# PicoBoard.net
KiCad netlist of a schematic drawn in EAGLE
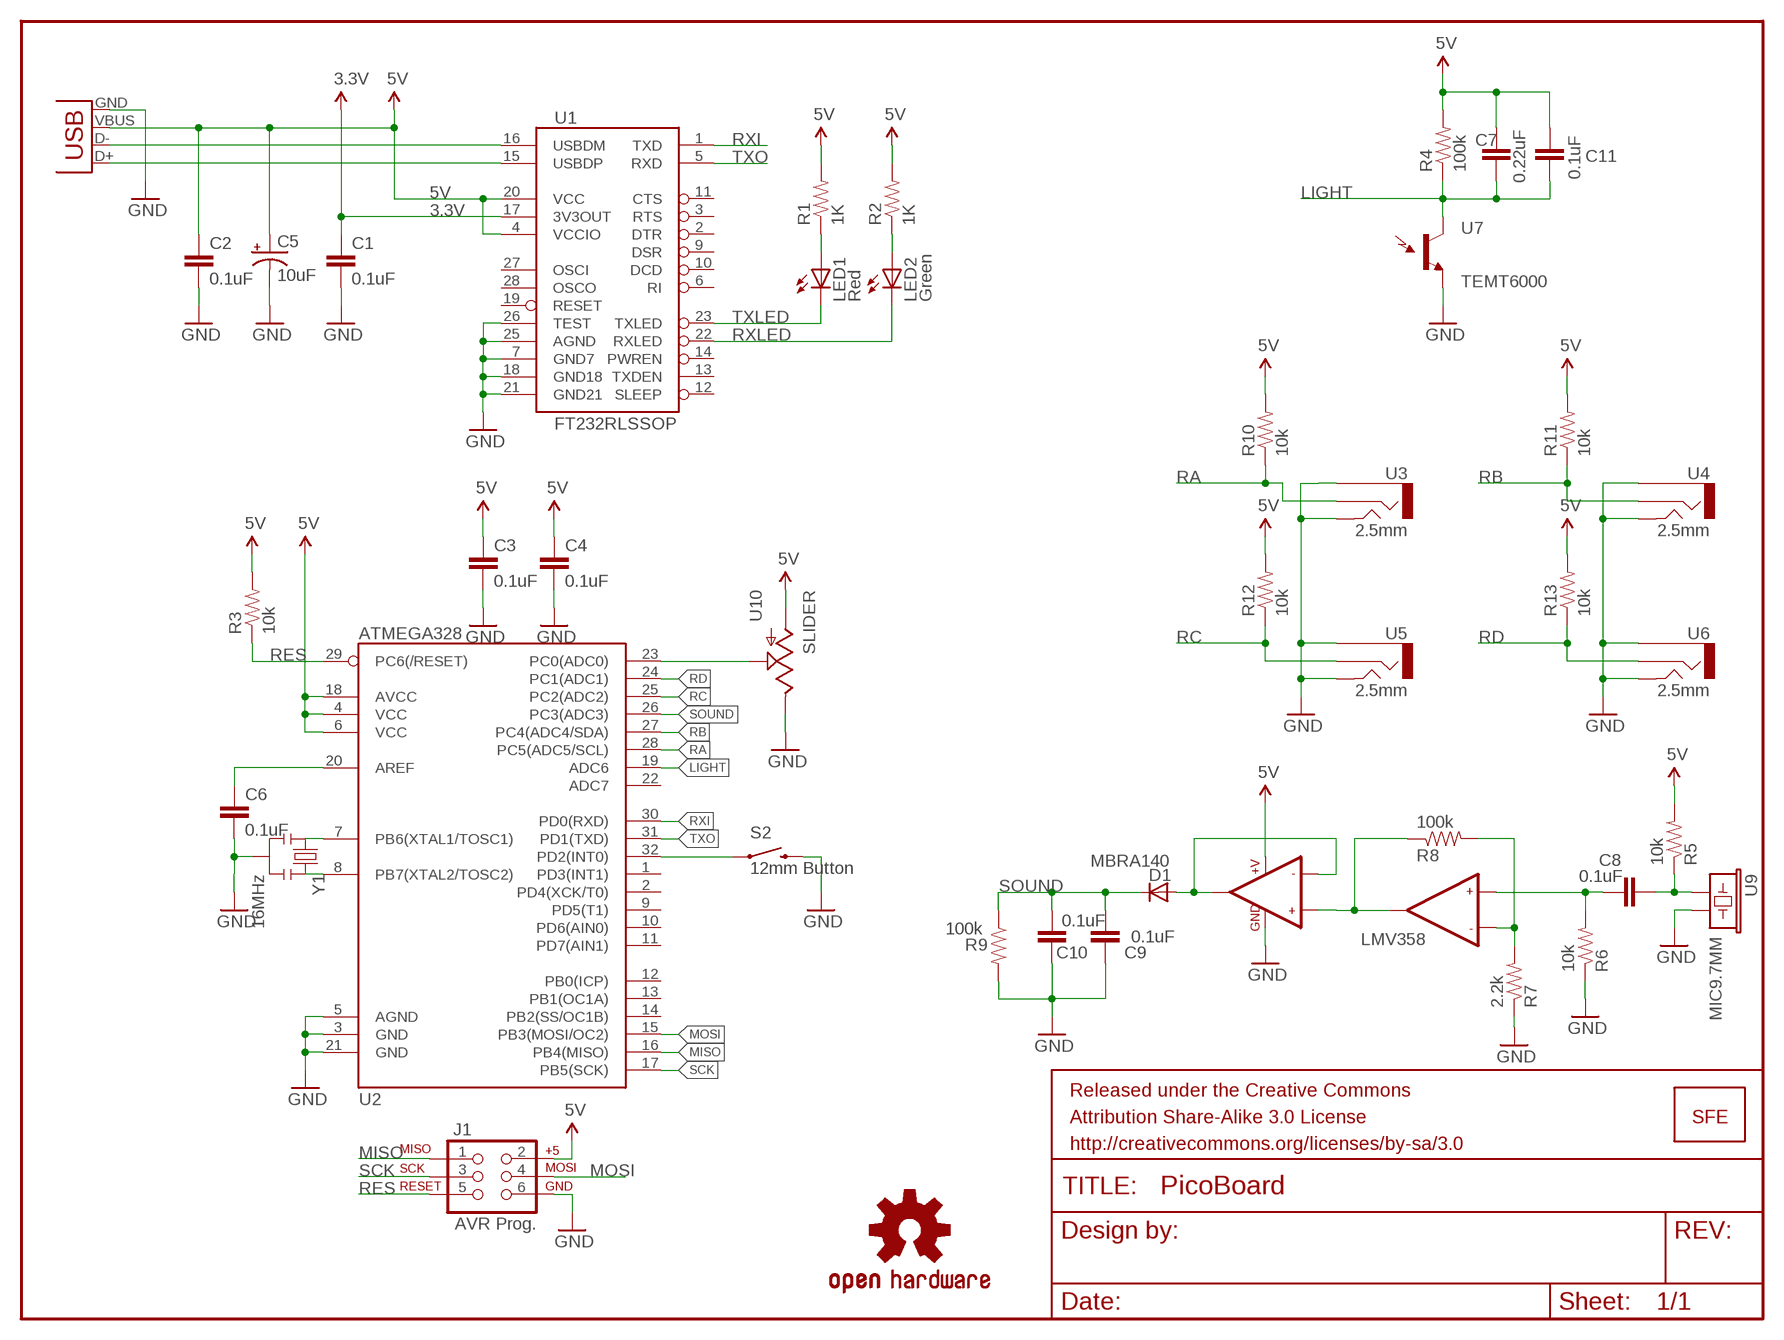
[diagram p0: schematic, sheet 1]

(export (version "E")
  (design (tool "Eeschema 10.0.6"))
  (components
    (comp (ref "C1")
      (value "0.1uF")
      (footprint "eagle-import:0603-CAP")
      (libsource (lib "eagle-import") (part "CAP0603-CAP"))
    )
    (comp (ref "C2")
      (value "0.1uF")
      (footprint "eagle-import:0603-CAP")
      (libsource (lib "eagle-import") (part "CAP0603-CAP"))
    )
    (comp (ref "C3")
      (value "0.1uF")
      (footprint "eagle-import:0603-CAP")
      (libsource (lib "eagle-import") (part "CAP0603-CAP"))
    )
    (comp (ref "C4")
      (value "0.1uF")
      (footprint "eagle-import:0603-CAP")
      (libsource (lib "eagle-import") (part "CAP0603-CAP"))
    )
    (comp (ref "C5")
      (value "10uF")
      (footprint "eagle-import:EIA3216")
      (libsource (lib "eagle-import") (part "CAP_POL1206"))
    )
    (comp (ref "C6")
      (value "0.1uF")
      (footprint "eagle-import:0603-CAP")
      (libsource (lib "eagle-import") (part "CAP0603-CAP"))
    )
    (comp (ref "C7")
      (value "0.22uF")
      (footprint "eagle-import:0603-CAP")
      (libsource (lib "eagle-import") (part "CAP0603-CAP"))
    )
    (comp (ref "C8")
      (value "0.1uF")
      (footprint "eagle-import:0603-CAP")
      (libsource (lib "eagle-import") (part "CAP0603-CAP"))
    )
    (comp (ref "C9")
      (value "0.1uF")
      (footprint "eagle-import:0603-CAP")
      (libsource (lib "eagle-import") (part "CAP0603-CAP"))
    )
    (comp (ref "C10")
      (value "0.1uF")
      (footprint "eagle-import:0603-CAP")
      (libsource (lib "eagle-import") (part "CAP0603-CAP"))
    )
    (comp (ref "C11")
      (value "0.1uF")
      (footprint "eagle-import:0603-CAP")
      (libsource (lib "eagle-import") (part "CAP0603-CAP"))
    )
    (comp (ref "D1")
      (value "MBRA140")
      (footprint "eagle-import:SMA-DIODE")
      (libsource (lib "eagle-import") (part "DIODESMA"))
    )
    (comp (ref "FRAME1")
      (value "FRAME-LETTER")
      (footprint "eagle-import:CREATIVE_COMMONS")
      (libsource (lib "eagle-import") (part "FRAME-LETTER"))
    )
    (comp (ref "J1")
      (value "AVR Prog.")
      (footprint "eagle-import:2X3")
      (libsource (lib "eagle-import") (part "AVR_SPI_PRG_6PTH"))
    )
    (comp (ref "JP1")
      (value "LOGO-SFENEW")
      (footprint "eagle-import:SFE-NEW-WEBLOGO")
      (libsource (lib "eagle-import") (part "LOGO-SFENEW"))
    )
    (comp (ref "LED1")
      (value "Red")
      (footprint "eagle-import:LED-0603")
      (libsource (lib "eagle-import") (part "LED0603"))
    )
    (comp (ref "LED2")
      (value "Green")
      (footprint "eagle-import:LED-0603")
      (libsource (lib "eagle-import") (part "LED0603"))
    )
    (comp (ref "LOGO1")
      (value "OSHW-LOGOL")
      (footprint "eagle-import:OSHW-LOGO-L")
      (libsource (lib "eagle-import") (part "OSHW-LOGOL"))
    )
    (comp (ref "R1")
      (value "1K")
      (footprint "eagle-import:0603-RES")
      (libsource (lib "eagle-import") (part "RESISTOR0603-RES"))
    )
    (comp (ref "R2")
      (value "1K")
      (footprint "eagle-import:0603-RES")
      (libsource (lib "eagle-import") (part "RESISTOR0603-RES"))
    )
    (comp (ref "R3")
      (value "10k")
      (footprint "eagle-import:0603-RES")
      (libsource (lib "eagle-import") (part "RESISTOR0603-RES"))
    )
    (comp (ref "R4")
      (value "100k")
      (footprint "eagle-import:0603-RES")
      (libsource (lib "eagle-import") (part "RESISTOR0603-RES"))
    )
    (comp (ref "R5")
      (value "10k")
      (footprint "eagle-import:0603-RES")
      (libsource (lib "eagle-import") (part "RESISTOR0603-RES"))
    )
    (comp (ref "R6")
      (value "10k")
      (footprint "eagle-import:0603-RES")
      (libsource (lib "eagle-import") (part "RESISTOR0603-RES"))
    )
    (comp (ref "R7")
      (value "2.2k")
      (footprint "eagle-import:0603-RES")
      (libsource (lib "eagle-import") (part "RESISTOR0603-RES"))
    )
    (comp (ref "R8")
      (value "100k")
      (footprint "eagle-import:0603-RES")
      (libsource (lib "eagle-import") (part "RESISTOR0603-RES"))
    )
    (comp (ref "R9")
      (value "100k")
      (footprint "eagle-import:0603-RES")
      (libsource (lib "eagle-import") (part "RESISTOR0603-RES"))
    )
    (comp (ref "R10")
      (value "10k")
      (footprint "eagle-import:0603-RES")
      (libsource (lib "eagle-import") (part "RESISTOR0603-RES"))
    )
    (comp (ref "R11")
      (value "10k")
      (footprint "eagle-import:0603-RES")
      (libsource (lib "eagle-import") (part "RESISTOR0603-RES"))
    )
    (comp (ref "R12")
      (value "10k")
      (footprint "eagle-import:0603-RES")
      (libsource (lib "eagle-import") (part "RESISTOR0603-RES"))
    )
    (comp (ref "R13")
      (value "10k")
      (footprint "eagle-import:0603-RES")
      (libsource (lib "eagle-import") (part "RESISTOR0603-RES"))
    )
    (comp (ref "S2")
      (value "12mm Button")
      (footprint "eagle-import:TACTILE-PTH-12MM")
      (libsource (lib "eagle-import") (part "SWITCH-MOMENTARY-212MM"))
    )
    (comp (ref "U1")
      (value "FT232RLSSOP")
      (footprint "eagle-import:SSOP28DB")
      (libsource (lib "eagle-import") (part "FT232RLSSOP"))
    )
    (comp (ref "U2")
      (value "ATMEGA328")
      (footprint "eagle-import:TQFP32-08")
      (libsource (lib "eagle-import") (part "ATMEGA168"))
    )
    (comp (ref "U3")
      (value "2.5mm")
      (footprint "eagle-import:STEREOJACK2.5MM_SMD")
      (libsource (lib "eagle-import") (part "AUDIO-JACKSMD"))
    )
    (comp (ref "U4")
      (value "2.5mm")
      (footprint "eagle-import:STEREOJACK2.5MM_SMD")
      (libsource (lib "eagle-import") (part "AUDIO-JACKSMD"))
    )
    (comp (ref "U5")
      (value "2.5mm")
      (footprint "eagle-import:STEREOJACK2.5MM_SMD")
      (libsource (lib "eagle-import") (part "AUDIO-JACKSMD"))
    )
    (comp (ref "U6")
      (value "2.5mm")
      (footprint "eagle-import:STEREOJACK2.5MM_SMD")
      (libsource (lib "eagle-import") (part "AUDIO-JACKSMD"))
    )
    (comp (ref "U7")
      (value "TEMT6000")
      (footprint "eagle-import:TEMT6000-SEN")
      (libsource (lib "eagle-import") (part "TEMT6000"))
    )
    (comp (ref "U8")
      (value "LMV358")
      (footprint "eagle-import:SO08")
      (libsource (lib "eagle-import") (part "LMV358"))
    )
    (comp (ref "U9")
      (value "MIC9.7MM")
      (footprint "eagle-import:MIC-9.7MM")
      (libsource (lib "eagle-import") (part "MIC9.7MM"))
    )
    (comp (ref "U10")
      (value "SLIDER")
      (footprint "eagle-import:SLIDER")
      (libsource (lib "eagle-import") (part "SLIDER"))
    )
    (comp (ref "X1")
      (value "USBSMD")
      (footprint "eagle-import:USB-MINIB")
      (libsource (lib "eagle-import") (part "USBSMD"))
    )
    (comp (ref "Y1")
      (value "16MHz")
      (footprint "eagle-import:RESONATOR-SMD")
      (libsource (lib "eagle-import") (part "RESONATORSMD"))
    )
  )
  (nets
    (net (code "1") (name "/RES") (class "Default")
      (node (ref "J1") (pin "5") (pinfunction "5_5") (pintype "passive"))
      (node (ref "R3") (pin "1") (pinfunction "1_1") (pintype "passive"))
      (node (ref "U2") (pin "29") (pinfunction "PC6(/RESET)_29") (pintype "bidirectional"))
    )
    (net (code "2") (name "/RXLED") (class "Default")
      (node (ref "LED2") (pin "C") (pinfunction "C_C") (pintype "passive"))
      (node (ref "U1") (pin "22") (pinfunction "RXLED_22") (pintype "input"))
    )
    (net (code "3") (name "/TXLED") (class "Default")
      (node (ref "LED1") (pin "C") (pinfunction "C_C") (pintype "passive"))
      (node (ref "U1") (pin "23") (pinfunction "TXLED_23") (pintype "input"))
    )
    (net (code "4") (name "3.3V") (class "Default")
      (node (ref "C1") (pin "1") (pinfunction "1_1") (pintype "passive"))
      (node (ref "U1") (pin "17") (pinfunction "3V3OUT_17") (pintype "output"))
    )
    (net (code "5") (name "5V") (class "Default")
      (node (ref "C11") (pin "1") (pinfunction "1_1") (pintype "passive"))
      (node (ref "C2") (pin "1") (pinfunction "1_1") (pintype "passive"))
      (node (ref "C3") (pin "1") (pinfunction "1_1") (pintype "passive"))
      (node (ref "C4") (pin "1") (pinfunction "1_1") (pintype "passive"))
      (node (ref "C5") (pin "A") (pinfunction "+_A") (pintype "passive"))
      (node (ref "C7") (pin "1") (pinfunction "1_1") (pintype "passive"))
      (node (ref "J1") (pin "2") (pinfunction "2_2") (pintype "passive"))
      (node (ref "R1") (pin "2") (pinfunction "2_2") (pintype "passive"))
      (node (ref "R10") (pin "2") (pinfunction "2_2") (pintype "passive"))
      (node (ref "R11") (pin "2") (pinfunction "2_2") (pintype "passive"))
      (node (ref "R12") (pin "2") (pinfunction "2_2") (pintype "passive"))
      (node (ref "R13") (pin "2") (pinfunction "2_2") (pintype "passive"))
      (node (ref "R2") (pin "2") (pinfunction "2_2") (pintype "passive"))
      (node (ref "R3") (pin "2") (pinfunction "2_2") (pintype "passive"))
      (node (ref "R4") (pin "2") (pinfunction "2_2") (pintype "passive"))
      (node (ref "R5") (pin "2") (pinfunction "2_2") (pintype "passive"))
      (node (ref "U1") (pin "20") (pinfunction "VCC_20") (pintype "power_in"))
      (node (ref "U1") (pin "4") (pinfunction "VCCIO_4") (pintype "power_in"))
      (node (ref "U10") (pin "3") (pinfunction "A_3") (pintype "passive"))
      (node (ref "U2") (pin "18") (pinfunction "AVCC_18") (pintype "bidirectional"))
      (node (ref "U2") (pin "4") (pinfunction "VCC_4") (pintype "bidirectional"))
      (node (ref "U2") (pin "6") (pinfunction "VCC_6") (pintype "bidirectional"))
      (node (ref "U8") (pin "8") (pinfunction "+V_8") (pintype "power_in"))
      (node (ref "X1") (pin "VBUS") (pinfunction "VBUS_VBUS") (pintype "bidirectional"))
    )
    (net (code "6") (name "GND") (class "Default")
      (node (ref "C1") (pin "2") (pinfunction "2_2") (pintype "passive"))
      (node (ref "C10") (pin "1") (pinfunction "1_1") (pintype "passive"))
      (node (ref "C2") (pin "2") (pinfunction "2_2") (pintype "passive"))
      (node (ref "C3") (pin "2") (pinfunction "2_2") (pintype "passive"))
      (node (ref "C4") (pin "2") (pinfunction "2_2") (pintype "passive"))
      (node (ref "C5") (pin "C") (pinfunction "-_C") (pintype "passive"))
      (node (ref "C6") (pin "2") (pinfunction "2_2") (pintype "passive"))
      (node (ref "C9") (pin "1") (pinfunction "1_1") (pintype "passive"))
      (node (ref "J1") (pin "6") (pinfunction "6_6") (pintype "passive"))
      (node (ref "R6") (pin "1") (pinfunction "1_1") (pintype "passive"))
      (node (ref "R7") (pin "1") (pinfunction "1_1") (pintype "passive"))
      (node (ref "R9") (pin "2") (pinfunction "2_2") (pintype "passive"))
      (node (ref "S2") (pin "3") (pinfunction "2_3") (pintype "passive"))
      (node (ref "U1") (pin "18") (pinfunction "GND18_18") (pintype "power_in"))
      (node (ref "U1") (pin "21") (pinfunction "GND21_21") (pintype "power_in"))
      (node (ref "U1") (pin "25") (pinfunction "AGND_25") (pintype "power_in"))
      (node (ref "U1") (pin "26") (pinfunction "TEST_26") (pintype "input"))
      (node (ref "U1") (pin "7") (pinfunction "GND7_7") (pintype "power_in"))
      (node (ref "U10") (pin "1") (pinfunction "E_1") (pintype "passive"))
      (node (ref "U2") (pin "21") (pinfunction "GND_21") (pintype "bidirectional"))
      (node (ref "U2") (pin "3") (pinfunction "GND_3") (pintype "bidirectional"))
      (node (ref "U2") (pin "5") (pinfunction "AGND_5") (pintype "bidirectional"))
      (node (ref "U3") (pin "1") (pinfunction "5_1") (pintype "bidirectional"))
      (node (ref "U3") (pin "5") (pinfunction "1_5") (pintype "bidirectional"))
      (node (ref "U4") (pin "1") (pinfunction "5_1") (pintype "bidirectional"))
      (node (ref "U4") (pin "5") (pinfunction "1_5") (pintype "bidirectional"))
      (node (ref "U5") (pin "1") (pinfunction "5_1") (pintype "bidirectional"))
      (node (ref "U5") (pin "5") (pinfunction "1_5") (pintype "bidirectional"))
      (node (ref "U6") (pin "1") (pinfunction "5_1") (pintype "bidirectional"))
      (node (ref "U6") (pin "5") (pinfunction "1_5") (pintype "bidirectional"))
      (node (ref "U7") (pin "EMITTER") (pinfunction "E1_EMITTER") (pintype "passive"))
      (node (ref "U8") (pin "4") (pinfunction "GND_4") (pintype "power_in"))
      (node (ref "U9") (pin "2") (pinfunction "2_2") (pintype "passive"))
      (node (ref "X1") (pin "GND") (pinfunction "GND_GND") (pintype "bidirectional"))
      (node (ref "Y1") (pin "2") (pinfunction "2_2") (pintype "passive"))
    )
    (net (code "7") (name "LIGHT") (class "Default")
      (node (ref "C11") (pin "2") (pinfunction "2_2") (pintype "passive"))
      (node (ref "C7") (pin "2") (pinfunction "2_2") (pintype "passive"))
      (node (ref "R4") (pin "1") (pinfunction "1_1") (pintype "passive"))
      (node (ref "U2") (pin "19") (pinfunction "ADC6_19") (pintype "bidirectional"))
      (node (ref "U7") (pin "COLLECTOR") (pinfunction "C1_COLLECTOR") (pintype "passive"))
    )
    (net (code "8") (name "MISO") (class "Default")
      (node (ref "J1") (pin "1") (pinfunction "1_1") (pintype "passive"))
      (node (ref "U2") (pin "16") (pinfunction "PB4(MISO)_16") (pintype "bidirectional"))
    )
    (net (code "9") (name "MOSI") (class "Default")
      (node (ref "J1") (pin "4") (pinfunction "4_4") (pintype "passive"))
      (node (ref "U2") (pin "15") (pinfunction "PB3(MOSI/OC2)_15") (pintype "bidirectional"))
    )
    (net (code "10") (name "Net-(C8-Pad1)") (class "Default")
      (node (ref "C8") (pin "1") (pinfunction "1_1") (pintype "passive"))
      (node (ref "R5") (pin "1") (pinfunction "1_1") (pintype "passive"))
      (node (ref "U9") (pin "1") (pinfunction "1_1") (pintype "passive"))
    )
    (net (code "11") (name "Net-(LED1-PadA)") (class "Default")
      (node (ref "LED1") (pin "A") (pinfunction "A_A") (pintype "passive"))
      (node (ref "R1") (pin "1") (pinfunction "1_1") (pintype "passive"))
    )
    (net (code "12") (name "Net-(LED2-PadA)") (class "Default")
      (node (ref "LED2") (pin "A") (pinfunction "A_A") (pintype "passive"))
      (node (ref "R2") (pin "1") (pinfunction "1_1") (pintype "passive"))
    )
    (net (code "13") (name "Net-(U1-USBDM)") (class "Default")
      (node (ref "U1") (pin "16") (pinfunction "USBDM_16") (pintype "bidirectional"))
      (node (ref "X1") (pin "D-") (pinfunction "D-_D-") (pintype "bidirectional"))
    )
    (net (code "14") (name "Net-(U1-USBDP)") (class "Default")
      (node (ref "U1") (pin "15") (pinfunction "USBDP_15") (pintype "bidirectional"))
      (node (ref "X1") (pin "D+") (pinfunction "D+_D+") (pintype "bidirectional"))
    )
    (net (code "15") (name "Net-(U2-AREF)") (class "Default")
      (node (ref "C6") (pin "1") (pinfunction "1_1") (pintype "passive"))
      (node (ref "U2") (pin "20") (pinfunction "AREF_20") (pintype "bidirectional"))
    )
    (net (code "16") (name "Net-(U2-PB6(XTAL1{slash}TOSC1))") (class "Default")
      (node (ref "U2") (pin "7") (pinfunction "PB6(XTAL1/TOSC1)_7") (pintype "bidirectional"))
      (node (ref "Y1") (pin "1") (pinfunction "1_1") (pintype "passive"))
    )
    (net (code "17") (name "Net-(U2-PB7(XTAL2{slash}TOSC2))") (class "Default")
      (node (ref "U2") (pin "8") (pinfunction "PB7(XTAL2/TOSC2)_8") (pintype "bidirectional"))
      (node (ref "Y1") (pin "3") (pinfunction "3_3") (pintype "passive"))
    )
    (net (code "18") (name "Net-(U2-PD2(INT0))") (class "Default")
      (node (ref "S2") (pin "1") (pinfunction "1_1") (pintype "passive"))
      (node (ref "U2") (pin "32") (pinfunction "PD2(INT0)_32") (pintype "bidirectional"))
    )
    (net (code "19") (name "Net-(U8A-+IN1)") (class "Default")
      (node (ref "R8") (pin "1") (pinfunction "1_1") (pintype "passive"))
      (node (ref "U8") (pin "3") (pinfunction "+IN1_3") (pintype "input"))
      (node (ref "U8") (pin "7") (pinfunction "OUT2_7") (pintype "output"))
    )
    (net (code "20") (name "Net-(U8A--IN1)") (class "Default")
      (node (ref "D1") (pin "A") (pinfunction "A_A") (pintype "passive"))
      (node (ref "U8") (pin "1") (pinfunction "OUT1_1") (pintype "output"))
      (node (ref "U8") (pin "2") (pinfunction "-IN1_2") (pintype "input"))
    )
    (net (code "21") (name "Net-(U8B-+IN2)") (class "Default")
      (node (ref "C8") (pin "2") (pinfunction "2_2") (pintype "passive"))
      (node (ref "R6") (pin "2") (pinfunction "2_2") (pintype "passive"))
      (node (ref "U8") (pin "5") (pinfunction "+IN2_5") (pintype "input"))
    )
    (net (code "22") (name "Net-(U8B--IN2)") (class "Default")
      (node (ref "R7") (pin "2") (pinfunction "2_2") (pintype "passive"))
      (node (ref "R8") (pin "2") (pinfunction "2_2") (pintype "passive"))
      (node (ref "U8") (pin "6") (pinfunction "-IN2_6") (pintype "input"))
    )
    (net (code "23") (name "Net-(U10-S)") (class "Default")
      (node (ref "U10") (pin "2A") (pinfunction "S_2A") (pintype "passive"))
      (node (ref "U2") (pin "23") (pinfunction "PC0(ADC0)_23") (pintype "bidirectional"))
    )
    (net (code "24") (name "RA") (class "Default")
      (node (ref "R10") (pin "1") (pinfunction "1_1") (pintype "passive"))
      (node (ref "U2") (pin "28") (pinfunction "PC5(ADC5/SCL)_28") (pintype "bidirectional"))
      (node (ref "U3") (pin "4") (pinfunction "2_4") (pintype "bidirectional"))
    )
    (net (code "25") (name "RB") (class "Default")
      (node (ref "R11") (pin "1") (pinfunction "1_1") (pintype "passive"))
      (node (ref "U2") (pin "27") (pinfunction "PC4(ADC4/SDA)_27") (pintype "bidirectional"))
      (node (ref "U4") (pin "4") (pinfunction "2_4") (pintype "bidirectional"))
    )
    (net (code "26") (name "RC") (class "Default")
      (node (ref "R12") (pin "1") (pinfunction "1_1") (pintype "passive"))
      (node (ref "U2") (pin "25") (pinfunction "PC2(ADC2)_25") (pintype "bidirectional"))
      (node (ref "U5") (pin "4") (pinfunction "2_4") (pintype "bidirectional"))
    )
    (net (code "27") (name "RD") (class "Default")
      (node (ref "R13") (pin "1") (pinfunction "1_1") (pintype "passive"))
      (node (ref "U2") (pin "24") (pinfunction "PC1(ADC1)_24") (pintype "bidirectional"))
      (node (ref "U6") (pin "4") (pinfunction "2_4") (pintype "bidirectional"))
    )
    (net (code "28") (name "RXI") (class "Default")
      (node (ref "U1") (pin "1") (pinfunction "TXD_1") (pintype "output"))
      (node (ref "U2") (pin "30") (pinfunction "PD0(RXD)_30") (pintype "bidirectional"))
    )
    (net (code "29") (name "SCK") (class "Default")
      (node (ref "J1") (pin "3") (pinfunction "3_3") (pintype "passive"))
      (node (ref "U2") (pin "17") (pinfunction "PB5(SCK)_17") (pintype "bidirectional"))
    )
    (net (code "30") (name "SOUND") (class "Default")
      (node (ref "C10") (pin "2") (pinfunction "2_2") (pintype "passive"))
      (node (ref "C9") (pin "2") (pinfunction "2_2") (pintype "passive"))
      (node (ref "D1") (pin "C") (pinfunction "C_C") (pintype "passive"))
      (node (ref "R9") (pin "1") (pinfunction "1_1") (pintype "passive"))
      (node (ref "U2") (pin "26") (pinfunction "PC3(ADC3)_26") (pintype "bidirectional"))
    )
    (net (code "31") (name "TXO") (class "Default")
      (node (ref "U1") (pin "5") (pinfunction "RXD_5") (pintype "input"))
      (node (ref "U2") (pin "31") (pinfunction "PD1(TXD)_31") (pintype "bidirectional"))
    )
    (net (code "32") (name "unconnected-(U1-CTS-Pad11)") (class "Default")
      (node (ref "U1") (pin "11") (pinfunction "CTS_11") (pintype "input"))
    )
    (net (code "33") (name "unconnected-(U1-DCD-Pad10)") (class "Default")
      (node (ref "U1") (pin "10") (pinfunction "DCD_10") (pintype "input"))
    )
    (net (code "34") (name "unconnected-(U1-DSR-Pad9)") (class "Default")
      (node (ref "U1") (pin "9") (pinfunction "DSR_9") (pintype "input"))
    )
    (net (code "35") (name "unconnected-(U1-DTR-Pad2)") (class "Default")
      (node (ref "U1") (pin "2") (pinfunction "DTR_2") (pintype "output"))
    )
    (net (code "36") (name "unconnected-(U1-OSCI-Pad27)") (class "Default")
      (node (ref "U1") (pin "27") (pinfunction "OSCI_27") (pintype "input"))
    )
    (net (code "37") (name "unconnected-(U1-OSCO-Pad28)") (class "Default")
      (node (ref "U1") (pin "28") (pinfunction "OSCO_28") (pintype "output"))
    )
    (net (code "38") (name "unconnected-(U1-PWREN-Pad14)") (class "Default")
      (node (ref "U1") (pin "14") (pinfunction "PWREN_14") (pintype "input"))
    )
    (net (code "39") (name "unconnected-(U1-RESET-Pad19)") (class "Default")
      (node (ref "U1") (pin "19") (pinfunction "RESET_19") (pintype "input"))
    )
    (net (code "40") (name "unconnected-(U1-RI-Pad6)") (class "Default")
      (node (ref "U1") (pin "6") (pinfunction "RI_6") (pintype "input"))
    )
    (net (code "41") (name "unconnected-(U1-RTS-Pad3)") (class "Default")
      (node (ref "U1") (pin "3") (pinfunction "RTS_3") (pintype "output"))
    )
    (net (code "42") (name "unconnected-(U1-SLEEP-Pad12)") (class "Default")
      (node (ref "U1") (pin "12") (pinfunction "SLEEP_12") (pintype "input"))
    )
    (net (code "43") (name "unconnected-(U1-TXDEN-Pad13)") (class "Default")
      (node (ref "U1") (pin "13") (pinfunction "TXDEN_13") (pintype "input"))
    )
    (net (code "44") (name "unconnected-(U2-ADC7-Pad22)") (class "Default")
      (node (ref "U2") (pin "22") (pinfunction "ADC7_22") (pintype "bidirectional"))
    )
    (net (code "45") (name "unconnected-(U2-PB0(ICP)-Pad12)") (class "Default")
      (node (ref "U2") (pin "12") (pinfunction "PB0(ICP)_12") (pintype "bidirectional"))
    )
    (net (code "46") (name "unconnected-(U2-PB1(OC1A)-Pad13)") (class "Default")
      (node (ref "U2") (pin "13") (pinfunction "PB1(OC1A)_13") (pintype "bidirectional"))
    )
    (net (code "47") (name "unconnected-(U2-PB2(SS{slash}OC1B)-Pad14)") (class "Default")
      (node (ref "U2") (pin "14") (pinfunction "PB2(SS/OC1B)_14") (pintype "bidirectional"))
    )
    (net (code "48") (name "unconnected-(U2-PD3(INT1)-Pad1)") (class "Default")
      (node (ref "U2") (pin "1") (pinfunction "PD3(INT1)_1") (pintype "bidirectional"))
    )
    (net (code "49") (name "unconnected-(U2-PD4(XCK{slash}T0)-Pad2)") (class "Default")
      (node (ref "U2") (pin "2") (pinfunction "PD4(XCK/T0)_2") (pintype "bidirectional"))
    )
    (net (code "50") (name "unconnected-(U2-PD5(T1)-Pad9)") (class "Default")
      (node (ref "U2") (pin "9") (pinfunction "PD5(T1)_9") (pintype "bidirectional"))
    )
    (net (code "51") (name "unconnected-(U2-PD6(AIN0)-Pad10)") (class "Default")
      (node (ref "U2") (pin "10") (pinfunction "PD6(AIN0)_10") (pintype "bidirectional"))
    )
    (net (code "52") (name "unconnected-(U2-PD7(AIN1)-Pad11)") (class "Default")
      (node (ref "U2") (pin "11") (pinfunction "PD7(AIN1)_11") (pintype "bidirectional"))
    )
  )
)
